# p6_led_matrix.net
KiCad netlist of a schematic drawn in Altium Designer
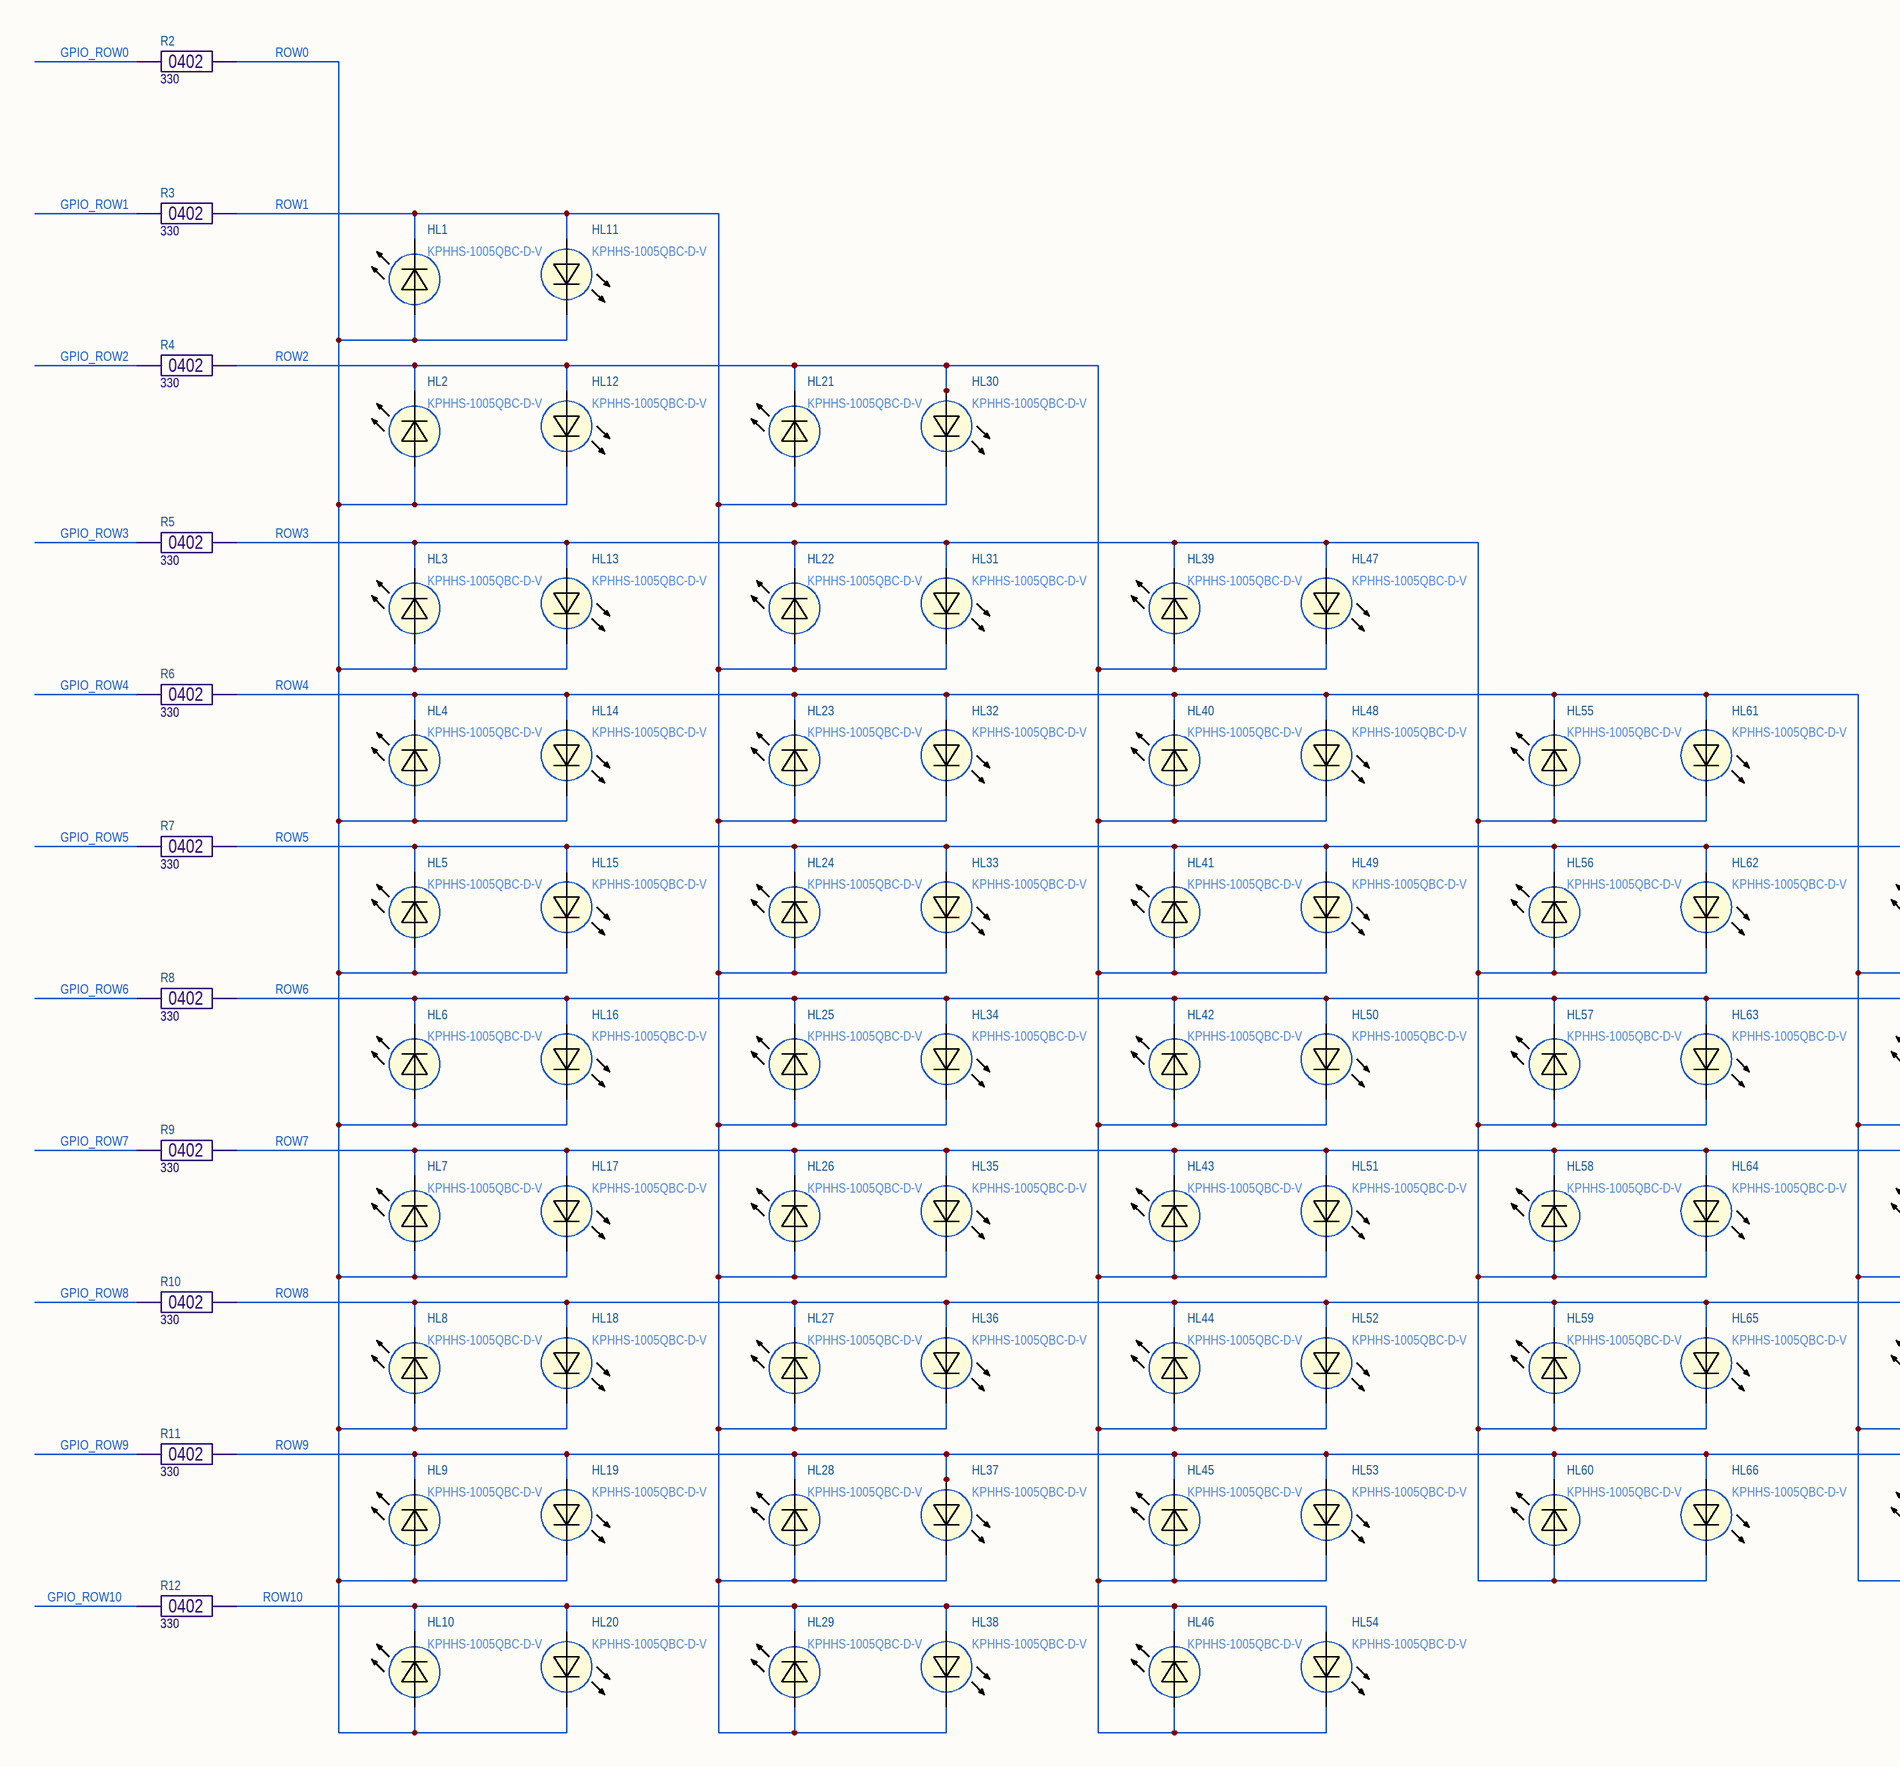
[diagram p0: p6_led_matrix.SchDoc, left]
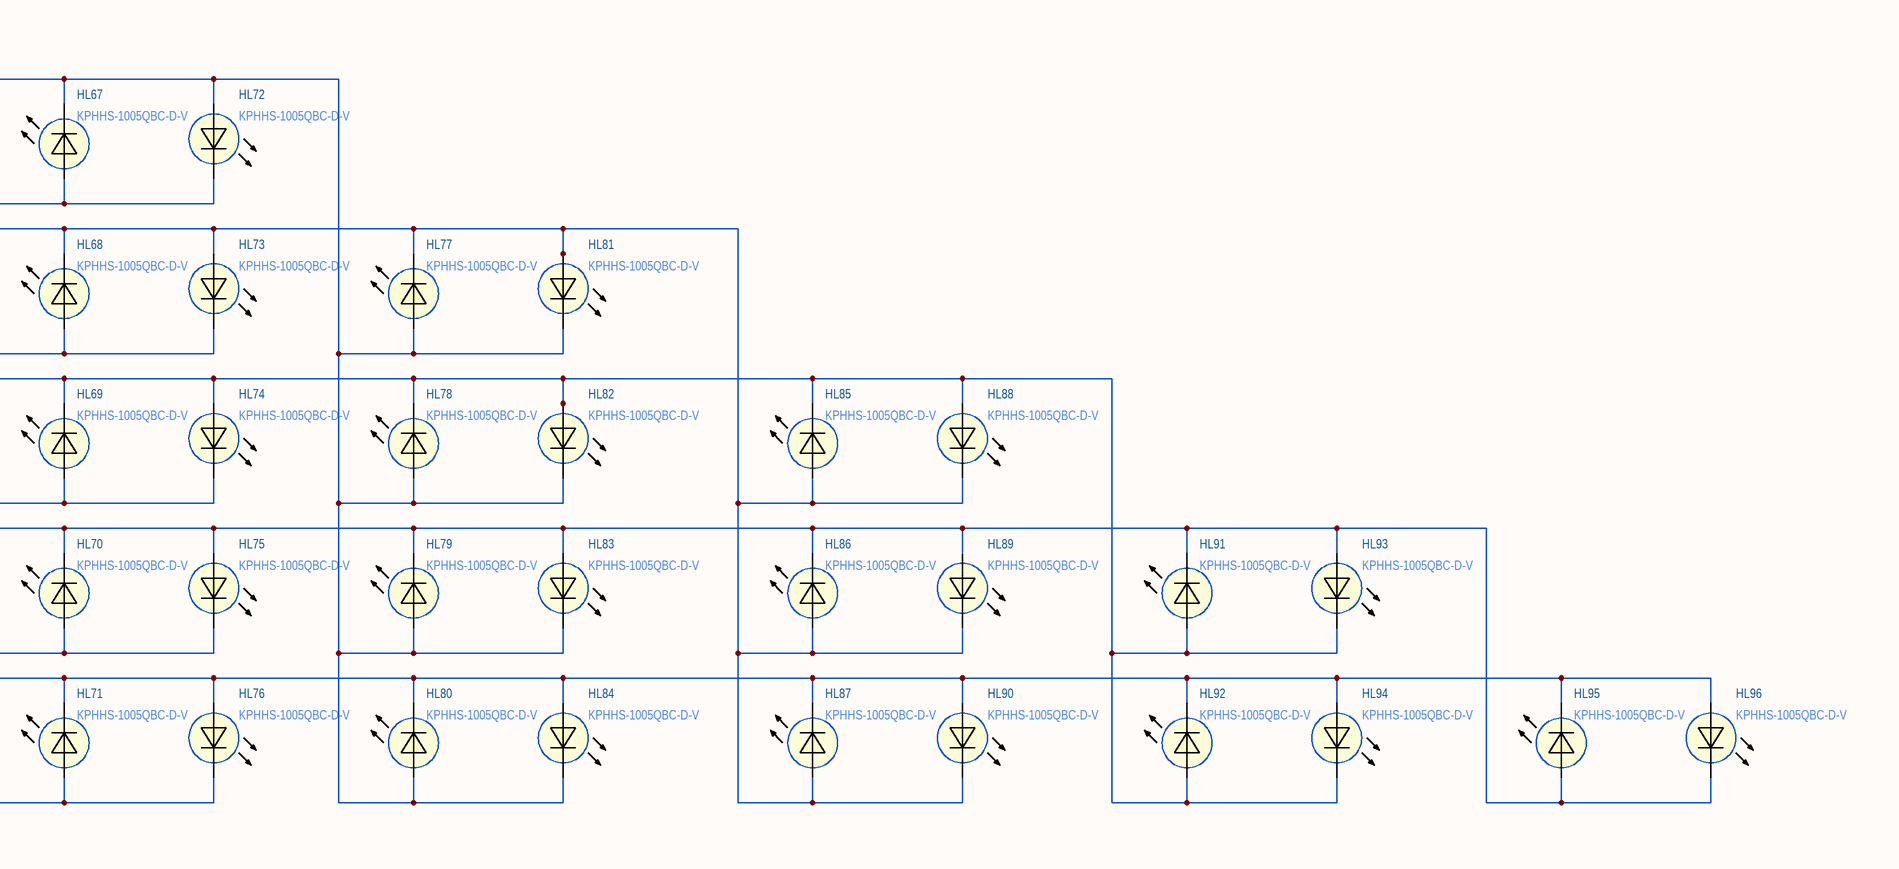
[diagram p1: p6_led_matrix.SchDoc, right]

(export (version "E")
  (design (tool "Eeschema 10.0.6"))
  (components
    (comp (ref "HL1")
      (value "KPHHS-1005QBC-D-V")
      (footprint "PcbLib_Others:LED0402B")
      (description "Blue led (package case 0402)")
      (fields (field (name "MANUFACTURER") "Kingbright Company LLC."))
      (libsource (lib "Schlib_Kingbright") (part "KPHHS-1005QBC-D-V"))
    )
    (comp (ref "HL2")
      (value "KPHHS-1005QBC-D-V")
      (footprint "PcbLib_Others:LED0402B")
      (description "Blue led (package case 0402)")
      (fields (field (name "MANUFACTURER") "Kingbright Company LLC."))
      (libsource (lib "Schlib_Kingbright") (part "KPHHS-1005QBC-D-V"))
    )
    (comp (ref "HL3")
      (value "KPHHS-1005QBC-D-V")
      (footprint "PcbLib_Others:LED0402B")
      (description "Blue led (package case 0402)")
      (fields (field (name "MANUFACTURER") "Kingbright Company LLC."))
      (libsource (lib "Schlib_Kingbright") (part "KPHHS-1005QBC-D-V"))
    )
    (comp (ref "HL4")
      (value "KPHHS-1005QBC-D-V")
      (footprint "PcbLib_Others:LED0402B")
      (description "Blue led (package case 0402)")
      (fields (field (name "MANUFACTURER") "Kingbright Company LLC."))
      (libsource (lib "Schlib_Kingbright") (part "KPHHS-1005QBC-D-V"))
    )
    (comp (ref "HL5")
      (value "KPHHS-1005QBC-D-V")
      (footprint "PcbLib_Others:LED0402B")
      (description "Blue led (package case 0402)")
      (fields (field (name "MANUFACTURER") "Kingbright Company LLC."))
      (libsource (lib "Schlib_Kingbright") (part "KPHHS-1005QBC-D-V"))
    )
    (comp (ref "HL6")
      (value "KPHHS-1005QBC-D-V")
      (footprint "PcbLib_Others:LED0402B")
      (description "Blue led (package case 0402)")
      (fields (field (name "MANUFACTURER") "Kingbright Company LLC."))
      (libsource (lib "Schlib_Kingbright") (part "KPHHS-1005QBC-D-V"))
    )
    (comp (ref "HL7")
      (value "KPHHS-1005QBC-D-V")
      (footprint "PcbLib_Others:LED0402B")
      (description "Blue led (package case 0402)")
      (fields (field (name "MANUFACTURER") "Kingbright Company LLC."))
      (libsource (lib "Schlib_Kingbright") (part "KPHHS-1005QBC-D-V"))
    )
    (comp (ref "HL8")
      (value "KPHHS-1005QBC-D-V")
      (footprint "PcbLib_Others:LED0402B")
      (description "Blue led (package case 0402)")
      (fields (field (name "MANUFACTURER") "Kingbright Company LLC."))
      (libsource (lib "Schlib_Kingbright") (part "KPHHS-1005QBC-D-V"))
    )
    (comp (ref "HL9")
      (value "KPHHS-1005QBC-D-V")
      (footprint "PcbLib_Others:LED0402B")
      (description "Blue led (package case 0402)")
      (fields (field (name "MANUFACTURER") "Kingbright Company LLC."))
      (libsource (lib "Schlib_Kingbright") (part "KPHHS-1005QBC-D-V"))
    )
    (comp (ref "HL10")
      (value "KPHHS-1005QBC-D-V")
      (footprint "PcbLib_Others:LED0402B")
      (description "Blue led (package case 0402)")
      (fields (field (name "MANUFACTURER") "Kingbright Company LLC."))
      (libsource (lib "Schlib_Kingbright") (part "KPHHS-1005QBC-D-V"))
    )
    (comp (ref "HL11")
      (value "KPHHS-1005QBC-D-V")
      (footprint "PcbLib_Others:LED0402B")
      (description "Blue led (package case 0402)")
      (fields (field (name "MANUFACTURER") "Kingbright Company LLC."))
      (libsource (lib "Schlib_Kingbright") (part "KPHHS-1005QBC-D-V"))
    )
    (comp (ref "HL12")
      (value "KPHHS-1005QBC-D-V")
      (footprint "PcbLib_Others:LED0402B")
      (description "Blue led (package case 0402)")
      (fields (field (name "MANUFACTURER") "Kingbright Company LLC."))
      (libsource (lib "Schlib_Kingbright") (part "KPHHS-1005QBC-D-V"))
    )
    (comp (ref "HL13")
      (value "KPHHS-1005QBC-D-V")
      (footprint "PcbLib_Others:LED0402B")
      (description "Blue led (package case 0402)")
      (fields (field (name "MANUFACTURER") "Kingbright Company LLC."))
      (libsource (lib "Schlib_Kingbright") (part "KPHHS-1005QBC-D-V"))
    )
    (comp (ref "HL14")
      (value "KPHHS-1005QBC-D-V")
      (footprint "PcbLib_Others:LED0402B")
      (description "Blue led (package case 0402)")
      (fields (field (name "MANUFACTURER") "Kingbright Company LLC."))
      (libsource (lib "Schlib_Kingbright") (part "KPHHS-1005QBC-D-V"))
    )
    (comp (ref "HL15")
      (value "KPHHS-1005QBC-D-V")
      (footprint "PcbLib_Others:LED0402B")
      (description "Blue led (package case 0402)")
      (fields (field (name "MANUFACTURER") "Kingbright Company LLC."))
      (libsource (lib "Schlib_Kingbright") (part "KPHHS-1005QBC-D-V"))
    )
    (comp (ref "HL16")
      (value "KPHHS-1005QBC-D-V")
      (footprint "PcbLib_Others:LED0402B")
      (description "Blue led (package case 0402)")
      (fields (field (name "MANUFACTURER") "Kingbright Company LLC."))
      (libsource (lib "Schlib_Kingbright") (part "KPHHS-1005QBC-D-V"))
    )
    (comp (ref "HL17")
      (value "KPHHS-1005QBC-D-V")
      (footprint "PcbLib_Others:LED0402B")
      (description "Blue led (package case 0402)")
      (fields (field (name "MANUFACTURER") "Kingbright Company LLC."))
      (libsource (lib "Schlib_Kingbright") (part "KPHHS-1005QBC-D-V"))
    )
    (comp (ref "HL18")
      (value "KPHHS-1005QBC-D-V")
      (footprint "PcbLib_Others:LED0402B")
      (description "Blue led (package case 0402)")
      (fields (field (name "MANUFACTURER") "Kingbright Company LLC."))
      (libsource (lib "Schlib_Kingbright") (part "KPHHS-1005QBC-D-V"))
    )
    (comp (ref "HL19")
      (value "KPHHS-1005QBC-D-V")
      (footprint "PcbLib_Others:LED0402B")
      (description "Blue led (package case 0402)")
      (fields (field (name "MANUFACTURER") "Kingbright Company LLC."))
      (libsource (lib "Schlib_Kingbright") (part "KPHHS-1005QBC-D-V"))
    )
    (comp (ref "HL20")
      (value "KPHHS-1005QBC-D-V")
      (footprint "PcbLib_Others:LED0402B")
      (description "Blue led (package case 0402)")
      (fields (field (name "MANUFACTURER") "Kingbright Company LLC."))
      (libsource (lib "Schlib_Kingbright") (part "KPHHS-1005QBC-D-V"))
    )
    (comp (ref "HL21")
      (value "KPHHS-1005QBC-D-V")
      (footprint "PcbLib_Others:LED0402B")
      (description "Blue led (package case 0402)")
      (fields (field (name "MANUFACTURER") "Kingbright Company LLC."))
      (libsource (lib "Schlib_Kingbright") (part "KPHHS-1005QBC-D-V"))
    )
    (comp (ref "HL22")
      (value "KPHHS-1005QBC-D-V")
      (footprint "PcbLib_Others:LED0402B")
      (description "Blue led (package case 0402)")
      (fields (field (name "MANUFACTURER") "Kingbright Company LLC."))
      (libsource (lib "Schlib_Kingbright") (part "KPHHS-1005QBC-D-V"))
    )
    (comp (ref "HL23")
      (value "KPHHS-1005QBC-D-V")
      (footprint "PcbLib_Others:LED0402B")
      (description "Blue led (package case 0402)")
      (fields (field (name "MANUFACTURER") "Kingbright Company LLC."))
      (libsource (lib "Schlib_Kingbright") (part "KPHHS-1005QBC-D-V"))
    )
    (comp (ref "HL24")
      (value "KPHHS-1005QBC-D-V")
      (footprint "PcbLib_Others:LED0402B")
      (description "Blue led (package case 0402)")
      (fields (field (name "MANUFACTURER") "Kingbright Company LLC."))
      (libsource (lib "Schlib_Kingbright") (part "KPHHS-1005QBC-D-V"))
    )
    (comp (ref "HL25")
      (value "KPHHS-1005QBC-D-V")
      (footprint "PcbLib_Others:LED0402B")
      (description "Blue led (package case 0402)")
      (fields (field (name "MANUFACTURER") "Kingbright Company LLC."))
      (libsource (lib "Schlib_Kingbright") (part "KPHHS-1005QBC-D-V"))
    )
    (comp (ref "HL26")
      (value "KPHHS-1005QBC-D-V")
      (footprint "PcbLib_Others:LED0402B")
      (description "Blue led (package case 0402)")
      (fields (field (name "MANUFACTURER") "Kingbright Company LLC."))
      (libsource (lib "Schlib_Kingbright") (part "KPHHS-1005QBC-D-V"))
    )
    (comp (ref "HL27")
      (value "KPHHS-1005QBC-D-V")
      (footprint "PcbLib_Others:LED0402B")
      (description "Blue led (package case 0402)")
      (fields (field (name "MANUFACTURER") "Kingbright Company LLC."))
      (libsource (lib "Schlib_Kingbright") (part "KPHHS-1005QBC-D-V"))
    )
    (comp (ref "HL28")
      (value "KPHHS-1005QBC-D-V")
      (footprint "PcbLib_Others:LED0402B")
      (description "Blue led (package case 0402)")
      (fields (field (name "MANUFACTURER") "Kingbright Company LLC."))
      (libsource (lib "Schlib_Kingbright") (part "KPHHS-1005QBC-D-V"))
    )
    (comp (ref "HL29")
      (value "KPHHS-1005QBC-D-V")
      (footprint "PcbLib_Others:LED0402B")
      (description "Blue led (package case 0402)")
      (fields (field (name "MANUFACTURER") "Kingbright Company LLC."))
      (libsource (lib "Schlib_Kingbright") (part "KPHHS-1005QBC-D-V"))
    )
    (comp (ref "HL30")
      (value "KPHHS-1005QBC-D-V")
      (footprint "PcbLib_Others:LED0402B")
      (description "Blue led (package case 0402)")
      (fields (field (name "MANUFACTURER") "Kingbright Company LLC."))
      (libsource (lib "Schlib_Kingbright") (part "KPHHS-1005QBC-D-V"))
    )
    (comp (ref "HL31")
      (value "KPHHS-1005QBC-D-V")
      (footprint "PcbLib_Others:LED0402B")
      (description "Blue led (package case 0402)")
      (fields (field (name "MANUFACTURER") "Kingbright Company LLC."))
      (libsource (lib "Schlib_Kingbright") (part "KPHHS-1005QBC-D-V"))
    )
    (comp (ref "HL32")
      (value "KPHHS-1005QBC-D-V")
      (footprint "PcbLib_Others:LED0402B")
      (description "Blue led (package case 0402)")
      (fields (field (name "MANUFACTURER") "Kingbright Company LLC."))
      (libsource (lib "Schlib_Kingbright") (part "KPHHS-1005QBC-D-V"))
    )
    (comp (ref "HL33")
      (value "KPHHS-1005QBC-D-V")
      (footprint "PcbLib_Others:LED0402B")
      (description "Blue led (package case 0402)")
      (fields (field (name "MANUFACTURER") "Kingbright Company LLC."))
      (libsource (lib "Schlib_Kingbright") (part "KPHHS-1005QBC-D-V"))
    )
    (comp (ref "HL34")
      (value "KPHHS-1005QBC-D-V")
      (footprint "PcbLib_Others:LED0402B")
      (description "Blue led (package case 0402)")
      (fields (field (name "MANUFACTURER") "Kingbright Company LLC."))
      (libsource (lib "Schlib_Kingbright") (part "KPHHS-1005QBC-D-V"))
    )
    (comp (ref "HL35")
      (value "KPHHS-1005QBC-D-V")
      (footprint "PcbLib_Others:LED0402B")
      (description "Blue led (package case 0402)")
      (fields (field (name "MANUFACTURER") "Kingbright Company LLC."))
      (libsource (lib "Schlib_Kingbright") (part "KPHHS-1005QBC-D-V"))
    )
    (comp (ref "HL36")
      (value "KPHHS-1005QBC-D-V")
      (footprint "PcbLib_Others:LED0402B")
      (description "Blue led (package case 0402)")
      (fields (field (name "MANUFACTURER") "Kingbright Company LLC."))
      (libsource (lib "Schlib_Kingbright") (part "KPHHS-1005QBC-D-V"))
    )
    (comp (ref "HL37")
      (value "KPHHS-1005QBC-D-V")
      (footprint "PcbLib_Others:LED0402B")
      (description "Blue led (package case 0402)")
      (fields (field (name "MANUFACTURER") "Kingbright Company LLC."))
      (libsource (lib "Schlib_Kingbright") (part "KPHHS-1005QBC-D-V"))
    )
    (comp (ref "HL38")
      (value "KPHHS-1005QBC-D-V")
      (footprint "PcbLib_Others:LED0402B")
      (description "Blue led (package case 0402)")
      (fields (field (name "MANUFACTURER") "Kingbright Company LLC."))
      (libsource (lib "Schlib_Kingbright") (part "KPHHS-1005QBC-D-V"))
    )
    (comp (ref "HL39")
      (value "KPHHS-1005QBC-D-V")
      (footprint "PcbLib_Others:LED0402B")
      (description "Blue led (package case 0402)")
      (fields (field (name "MANUFACTURER") "Kingbright Company LLC."))
      (libsource (lib "Schlib_Kingbright") (part "KPHHS-1005QBC-D-V"))
    )
    (comp (ref "HL40")
      (value "KPHHS-1005QBC-D-V")
      (footprint "PcbLib_Others:LED0402B")
      (description "Blue led (package case 0402)")
      (fields (field (name "MANUFACTURER") "Kingbright Company LLC."))
      (libsource (lib "Schlib_Kingbright") (part "KPHHS-1005QBC-D-V"))
    )
    (comp (ref "HL41")
      (value "KPHHS-1005QBC-D-V")
      (footprint "PcbLib_Others:LED0402B")
      (description "Blue led (package case 0402)")
      (fields (field (name "MANUFACTURER") "Kingbright Company LLC."))
      (libsource (lib "Schlib_Kingbright") (part "KPHHS-1005QBC-D-V"))
    )
    (comp (ref "HL42")
      (value "KPHHS-1005QBC-D-V")
      (footprint "PcbLib_Others:LED0402B")
      (description "Blue led (package case 0402)")
      (fields (field (name "MANUFACTURER") "Kingbright Company LLC."))
      (libsource (lib "Schlib_Kingbright") (part "KPHHS-1005QBC-D-V"))
    )
    (comp (ref "HL43")
      (value "KPHHS-1005QBC-D-V")
      (footprint "PcbLib_Others:LED0402B")
      (description "Blue led (package case 0402)")
      (fields (field (name "MANUFACTURER") "Kingbright Company LLC."))
      (libsource (lib "Schlib_Kingbright") (part "KPHHS-1005QBC-D-V"))
    )
    (comp (ref "HL44")
      (value "KPHHS-1005QBC-D-V")
      (footprint "PcbLib_Others:LED0402B")
      (description "Blue led (package case 0402)")
      (fields (field (name "MANUFACTURER") "Kingbright Company LLC."))
      (libsource (lib "Schlib_Kingbright") (part "KPHHS-1005QBC-D-V"))
    )
    (comp (ref "HL45")
      (value "KPHHS-1005QBC-D-V")
      (footprint "PcbLib_Others:LED0402B")
      (description "Blue led (package case 0402)")
      (fields (field (name "MANUFACTURER") "Kingbright Company LLC."))
      (libsource (lib "Schlib_Kingbright") (part "KPHHS-1005QBC-D-V"))
    )
    (comp (ref "HL46")
      (value "KPHHS-1005QBC-D-V")
      (footprint "PcbLib_Others:LED0402B")
      (description "Blue led (package case 0402)")
      (fields (field (name "MANUFACTURER") "Kingbright Company LLC."))
      (libsource (lib "Schlib_Kingbright") (part "KPHHS-1005QBC-D-V"))
    )
    (comp (ref "HL47")
      (value "KPHHS-1005QBC-D-V")
      (footprint "PcbLib_Others:LED0402B")
      (description "Blue led (package case 0402)")
      (fields (field (name "MANUFACTURER") "Kingbright Company LLC."))
      (libsource (lib "Schlib_Kingbright") (part "KPHHS-1005QBC-D-V"))
    )
    (comp (ref "HL48")
      (value "KPHHS-1005QBC-D-V")
      (footprint "PcbLib_Others:LED0402B")
      (description "Blue led (package case 0402)")
      (fields (field (name "MANUFACTURER") "Kingbright Company LLC."))
      (libsource (lib "Schlib_Kingbright") (part "KPHHS-1005QBC-D-V"))
    )
    (comp (ref "HL49")
      (value "KPHHS-1005QBC-D-V")
      (footprint "PcbLib_Others:LED0402B")
      (description "Blue led (package case 0402)")
      (fields (field (name "MANUFACTURER") "Kingbright Company LLC."))
      (libsource (lib "Schlib_Kingbright") (part "KPHHS-1005QBC-D-V"))
    )
    (comp (ref "HL50")
      (value "KPHHS-1005QBC-D-V")
      (footprint "PcbLib_Others:LED0402B")
      (description "Blue led (package case 0402)")
      (fields (field (name "MANUFACTURER") "Kingbright Company LLC."))
      (libsource (lib "Schlib_Kingbright") (part "KPHHS-1005QBC-D-V"))
    )
    (comp (ref "HL51")
      (value "KPHHS-1005QBC-D-V")
      (footprint "PcbLib_Others:LED0402B")
      (description "Blue led (package case 0402)")
      (fields (field (name "MANUFACTURER") "Kingbright Company LLC."))
      (libsource (lib "Schlib_Kingbright") (part "KPHHS-1005QBC-D-V"))
    )
    (comp (ref "HL52")
      (value "KPHHS-1005QBC-D-V")
      (footprint "PcbLib_Others:LED0402B")
      (description "Blue led (package case 0402)")
      (fields (field (name "MANUFACTURER") "Kingbright Company LLC."))
      (libsource (lib "Schlib_Kingbright") (part "KPHHS-1005QBC-D-V"))
    )
    (comp (ref "HL53")
      (value "KPHHS-1005QBC-D-V")
      (footprint "PcbLib_Others:LED0402B")
      (description "Blue led (package case 0402)")
      (fields (field (name "MANUFACTURER") "Kingbright Company LLC."))
      (libsource (lib "Schlib_Kingbright") (part "KPHHS-1005QBC-D-V"))
    )
    (comp (ref "HL54")
      (value "KPHHS-1005QBC-D-V")
      (footprint "PcbLib_Others:LED0402B")
      (description "Blue led (package case 0402)")
      (fields (field (name "MANUFACTURER") "Kingbright Company LLC."))
      (libsource (lib "Schlib_Kingbright") (part "KPHHS-1005QBC-D-V"))
    )
    (comp (ref "HL55")
      (value "KPHHS-1005QBC-D-V")
      (footprint "PcbLib_Others:LED0402B")
      (description "Blue led (package case 0402)")
      (fields (field (name "MANUFACTURER") "Kingbright Company LLC."))
      (libsource (lib "Schlib_Kingbright") (part "KPHHS-1005QBC-D-V"))
    )
    (comp (ref "HL56")
      (value "KPHHS-1005QBC-D-V")
      (footprint "PcbLib_Others:LED0402B")
      (description "Blue led (package case 0402)")
      (fields (field (name "MANUFACTURER") "Kingbright Company LLC."))
      (libsource (lib "Schlib_Kingbright") (part "KPHHS-1005QBC-D-V"))
    )
    (comp (ref "HL57")
      (value "KPHHS-1005QBC-D-V")
      (footprint "PcbLib_Others:LED0402B")
      (description "Blue led (package case 0402)")
      (fields (field (name "MANUFACTURER") "Kingbright Company LLC."))
      (libsource (lib "Schlib_Kingbright") (part "KPHHS-1005QBC-D-V"))
    )
    (comp (ref "HL58")
      (value "KPHHS-1005QBC-D-V")
      (footprint "PcbLib_Others:LED0402B")
      (description "Blue led (package case 0402)")
      (fields (field (name "MANUFACTURER") "Kingbright Company LLC."))
      (libsource (lib "Schlib_Kingbright") (part "KPHHS-1005QBC-D-V"))
    )
    (comp (ref "HL59")
      (value "KPHHS-1005QBC-D-V")
      (footprint "PcbLib_Others:LED0402B")
      (description "Blue led (package case 0402)")
      (fields (field (name "MANUFACTURER") "Kingbright Company LLC."))
      (libsource (lib "Schlib_Kingbright") (part "KPHHS-1005QBC-D-V"))
    )
    (comp (ref "HL60")
      (value "KPHHS-1005QBC-D-V")
      (footprint "PcbLib_Others:LED0402B")
      (description "Blue led (package case 0402)")
      (fields (field (name "MANUFACTURER") "Kingbright Company LLC."))
      (libsource (lib "Schlib_Kingbright") (part "KPHHS-1005QBC-D-V"))
    )
    (comp (ref "HL61")
      (value "KPHHS-1005QBC-D-V")
      (footprint "PcbLib_Others:LED0402B")
      (description "Blue led (package case 0402)")
      (fields (field (name "MANUFACTURER") "Kingbright Company LLC."))
      (libsource (lib "Schlib_Kingbright") (part "KPHHS-1005QBC-D-V"))
    )
    (comp (ref "HL62")
      (value "KPHHS-1005QBC-D-V")
      (footprint "PcbLib_Others:LED0402B")
      (description "Blue led (package case 0402)")
      (fields (field (name "MANUFACTURER") "Kingbright Company LLC."))
      (libsource (lib "Schlib_Kingbright") (part "KPHHS-1005QBC-D-V"))
    )
    (comp (ref "HL63")
      (value "KPHHS-1005QBC-D-V")
      (footprint "PcbLib_Others:LED0402B")
      (description "Blue led (package case 0402)")
      (fields (field (name "MANUFACTURER") "Kingbright Company LLC."))
      (libsource (lib "Schlib_Kingbright") (part "KPHHS-1005QBC-D-V"))
    )
    (comp (ref "HL64")
      (value "KPHHS-1005QBC-D-V")
      (footprint "PcbLib_Others:LED0402B")
      (description "Blue led (package case 0402)")
      (fields (field (name "MANUFACTURER") "Kingbright Company LLC."))
      (libsource (lib "Schlib_Kingbright") (part "KPHHS-1005QBC-D-V"))
    )
    (comp (ref "HL65")
      (value "KPHHS-1005QBC-D-V")
      (footprint "PcbLib_Others:LED0402B")
      (description "Blue led (package case 0402)")
      (fields (field (name "MANUFACTURER") "Kingbright Company LLC."))
      (libsource (lib "Schlib_Kingbright") (part "KPHHS-1005QBC-D-V"))
    )
    (comp (ref "HL66")
      (value "KPHHS-1005QBC-D-V")
      (footprint "PcbLib_Others:LED0402B")
      (description "Blue led (package case 0402)")
      (fields (field (name "MANUFACTURER") "Kingbright Company LLC."))
      (libsource (lib "Schlib_Kingbright") (part "KPHHS-1005QBC-D-V"))
    )
    (comp (ref "HL67")
      (value "KPHHS-1005QBC-D-V")
      (footprint "PcbLib_Others:LED0402B")
      (description "Blue led (package case 0402)")
      (fields (field (name "MANUFACTURER") "Kingbright Company LLC."))
      (libsource (lib "Schlib_Kingbright") (part "KPHHS-1005QBC-D-V"))
    )
    (comp (ref "HL68")
      (value "KPHHS-1005QBC-D-V")
      (footprint "PcbLib_Others:LED0402B")
      (description "Blue led (package case 0402)")
      (fields (field (name "MANUFACTURER") "Kingbright Company LLC."))
      (libsource (lib "Schlib_Kingbright") (part "KPHHS-1005QBC-D-V"))
    )
    (comp (ref "HL69")
      (value "KPHHS-1005QBC-D-V")
      (footprint "PcbLib_Others:LED0402B")
      (description "Blue led (package case 0402)")
      (fields (field (name "MANUFACTURER") "Kingbright Company LLC."))
      (libsource (lib "Schlib_Kingbright") (part "KPHHS-1005QBC-D-V"))
    )
    (comp (ref "HL70")
      (value "KPHHS-1005QBC-D-V")
      (footprint "PcbLib_Others:LED0402B")
      (description "Blue led (package case 0402)")
      (fields (field (name "MANUFACTURER") "Kingbright Company LLC."))
      (libsource (lib "Schlib_Kingbright") (part "KPHHS-1005QBC-D-V"))
    )
    (comp (ref "HL71")
      (value "KPHHS-1005QBC-D-V")
      (footprint "PcbLib_Others:LED0402B")
      (description "Blue led (package case 0402)")
      (fields (field (name "MANUFACTURER") "Kingbright Company LLC."))
      (libsource (lib "Schlib_Kingbright") (part "KPHHS-1005QBC-D-V"))
    )
    (comp (ref "HL72")
      (value "KPHHS-1005QBC-D-V")
      (footprint "PcbLib_Others:LED0402B")
      (description "Blue led (package case 0402)")
      (fields (field (name "MANUFACTURER") "Kingbright Company LLC."))
      (libsource (lib "Schlib_Kingbright") (part "KPHHS-1005QBC-D-V"))
    )
    (comp (ref "HL73")
      (value "KPHHS-1005QBC-D-V")
      (footprint "PcbLib_Others:LED0402B")
      (description "Blue led (package case 0402)")
      (fields (field (name "MANUFACTURER") "Kingbright Company LLC."))
      (libsource (lib "Schlib_Kingbright") (part "KPHHS-1005QBC-D-V"))
    )
    (comp (ref "HL74")
      (value "KPHHS-1005QBC-D-V")
      (footprint "PcbLib_Others:LED0402B")
      (description "Blue led (package case 0402)")
      (fields (field (name "MANUFACTURER") "Kingbright Company LLC."))
      (libsource (lib "Schlib_Kingbright") (part "KPHHS-1005QBC-D-V"))
    )
    (comp (ref "HL75")
      (value "KPHHS-1005QBC-D-V")
      (footprint "PcbLib_Others:LED0402B")
      (description "Blue led (package case 0402)")
      (fields (field (name "MANUFACTURER") "Kingbright Company LLC."))
      (libsource (lib "Schlib_Kingbright") (part "KPHHS-1005QBC-D-V"))
    )
    (comp (ref "HL76")
      (value "KPHHS-1005QBC-D-V")
      (footprint "PcbLib_Others:LED0402B")
      (description "Blue led (package case 0402)")
      (fields (field (name "MANUFACTURER") "Kingbright Company LLC."))
      (libsource (lib "Schlib_Kingbright") (part "KPHHS-1005QBC-D-V"))
    )
    (comp (ref "HL77")
      (value "KPHHS-1005QBC-D-V")
      (footprint "PcbLib_Others:LED0402B")
      (description "Blue led (package case 0402)")
      (fields (field (name "MANUFACTURER") "Kingbright Company LLC."))
      (libsource (lib "Schlib_Kingbright") (part "KPHHS-1005QBC-D-V"))
    )
    (comp (ref "HL78")
      (value "KPHHS-1005QBC-D-V")
      (footprint "PcbLib_Others:LED0402B")
      (description "Blue led (package case 0402)")
      (fields (field (name "MANUFACTURER") "Kingbright Company LLC."))
      (libsource (lib "Schlib_Kingbright") (part "KPHHS-1005QBC-D-V"))
    )
    (comp (ref "HL79")
      (value "KPHHS-1005QBC-D-V")
      (footprint "PcbLib_Others:LED0402B")
      (description "Blue led (package case 0402)")
      (fields (field (name "MANUFACTURER") "Kingbright Company LLC."))
      (libsource (lib "Schlib_Kingbright") (part "KPHHS-1005QBC-D-V"))
    )
    (comp (ref "HL80")
      (value "KPHHS-1005QBC-D-V")
      (footprint "PcbLib_Others:LED0402B")
      (description "Blue led (package case 0402)")
      (fields (field (name "MANUFACTURER") "Kingbright Company LLC."))
      (libsource (lib "Schlib_Kingbright") (part "KPHHS-1005QBC-D-V"))
    )
    (comp (ref "HL81")
      (value "KPHHS-1005QBC-D-V")
      (footprint "PcbLib_Others:LED0402B")
      (description "Blue led (package case 0402)")
      (fields (field (name "MANUFACTURER") "Kingbright Company LLC."))
      (libsource (lib "Schlib_Kingbright") (part "KPHHS-1005QBC-D-V"))
    )
    (comp (ref "HL82")
      (value "KPHHS-1005QBC-D-V")
      (footprint "PcbLib_Others:LED0402B")
      (description "Blue led (package case 0402)")
      (fields (field (name "MANUFACTURER") "Kingbright Company LLC."))
      (libsource (lib "Schlib_Kingbright") (part "KPHHS-1005QBC-D-V"))
    )
    (comp (ref "HL83")
      (value "KPHHS-1005QBC-D-V")
      (footprint "PcbLib_Others:LED0402B")
      (description "Blue led (package case 0402)")
      (fields (field (name "MANUFACTURER") "Kingbright Company LLC."))
      (libsource (lib "Schlib_Kingbright") (part "KPHHS-1005QBC-D-V"))
    )
    (comp (ref "HL84")
      (value "KPHHS-1005QBC-D-V")
      (footprint "PcbLib_Others:LED0402B")
      (description "Blue led (package case 0402)")
      (fields (field (name "MANUFACTURER") "Kingbright Company LLC."))
      (libsource (lib "Schlib_Kingbright") (part "KPHHS-1005QBC-D-V"))
    )
    (comp (ref "HL85")
      (value "KPHHS-1005QBC-D-V")
      (footprint "PcbLib_Others:LED0402B")
      (description "Blue led (package case 0402)")
      (fields (field (name "MANUFACTURER") "Kingbright Company LLC."))
      (libsource (lib "Schlib_Kingbright") (part "KPHHS-1005QBC-D-V"))
    )
    (comp (ref "HL86")
      (value "KPHHS-1005QBC-D-V")
      (footprint "PcbLib_Others:LED0402B")
      (description "Blue led (package case 0402)")
      (fields (field (name "MANUFACTURER") "Kingbright Company LLC."))
      (libsource (lib "Schlib_Kingbright") (part "KPHHS-1005QBC-D-V"))
    )
    (comp (ref "HL87")
      (value "KPHHS-1005QBC-D-V")
      (footprint "PcbLib_Others:LED0402B")
      (description "Blue led (package case 0402)")
      (fields (field (name "MANUFACTURER") "Kingbright Company LLC."))
      (libsource (lib "Schlib_Kingbright") (part "KPHHS-1005QBC-D-V"))
    )
    (comp (ref "HL88")
      (value "KPHHS-1005QBC-D-V")
      (footprint "PcbLib_Others:LED0402B")
      (description "Blue led (package case 0402)")
      (fields (field (name "MANUFACTURER") "Kingbright Company LLC."))
      (libsource (lib "Schlib_Kingbright") (part "KPHHS-1005QBC-D-V"))
    )
    (comp (ref "HL89")
      (value "KPHHS-1005QBC-D-V")
      (footprint "PcbLib_Others:LED0402B")
      (description "Blue led (package case 0402)")
      (fields (field (name "MANUFACTURER") "Kingbright Company LLC."))
      (libsource (lib "Schlib_Kingbright") (part "KPHHS-1005QBC-D-V"))
    )
    (comp (ref "HL90")
      (value "KPHHS-1005QBC-D-V")
      (footprint "PcbLib_Others:LED0402B")
      (description "Blue led (package case 0402)")
      (fields (field (name "MANUFACTURER") "Kingbright Company LLC."))
      (libsource (lib "Schlib_Kingbright") (part "KPHHS-1005QBC-D-V"))
    )
    (comp (ref "HL91")
      (value "KPHHS-1005QBC-D-V")
      (footprint "PcbLib_Others:LED0402B")
      (description "Blue led (package case 0402)")
      (fields (field (name "MANUFACTURER") "Kingbright Company LLC."))
      (libsource (lib "Schlib_Kingbright") (part "KPHHS-1005QBC-D-V"))
    )
    (comp (ref "HL92")
      (value "KPHHS-1005QBC-D-V")
      (footprint "PcbLib_Others:LED0402B")
      (description "Blue led (package case 0402)")
      (fields (field (name "MANUFACTURER") "Kingbright Company LLC."))
      (libsource (lib "Schlib_Kingbright") (part "KPHHS-1005QBC-D-V"))
    )
    (comp (ref "HL93")
      (value "KPHHS-1005QBC-D-V")
      (footprint "PcbLib_Others:LED0402B")
      (description "Blue led (package case 0402)")
      (fields (field (name "MANUFACTURER") "Kingbright Company LLC."))
      (libsource (lib "Schlib_Kingbright") (part "KPHHS-1005QBC-D-V"))
    )
    (comp (ref "HL94")
      (value "KPHHS-1005QBC-D-V")
      (footprint "PcbLib_Others:LED0402B")
      (description "Blue led (package case 0402)")
      (fields (field (name "MANUFACTURER") "Kingbright Company LLC."))
      (libsource (lib "Schlib_Kingbright") (part "KPHHS-1005QBC-D-V"))
    )
    (comp (ref "HL95")
      (value "KPHHS-1005QBC-D-V")
      (footprint "PcbLib_Others:LED0402B")
      (description "Blue led (package case 0402)")
      (fields (field (name "MANUFACTURER") "Kingbright Company LLC."))
      (libsource (lib "Schlib_Kingbright") (part "KPHHS-1005QBC-D-V"))
    )
    (comp (ref "HL96")
      (value "KPHHS-1005QBC-D-V")
      (footprint "PcbLib_Others:LED0402B")
      (description "Blue led (package case 0402)")
      (fields (field (name "MANUFACTURER") "Kingbright Company LLC."))
      (libsource (lib "Schlib_Kingbright") (part "KPHHS-1005QBC-D-V"))
    )
    (comp (ref "R2")
      (value "330")
      (footprint "PcbLib_RC:RES0402B")
      (description "Resistor 0402 package case")
      (fields
        (field (name "TOLERANCE") "± 1 %")
        (field (name "PART NUMBER") "RC0402FR-07330RL")
        (field (name "PACKAGE") "0402")
      )
      (libsource (lib "Schlib_RC") (part "R0402"))
    )
    (comp (ref "R3")
      (value "330")
      (footprint "PcbLib_RC:RES0402B")
      (description "Resistor 0402 package case")
      (fields
        (field (name "TOLERANCE") "± 1 %")
        (field (name "PART NUMBER") "RC0402FR-07330RL")
        (field (name "PACKAGE") "0402")
      )
      (libsource (lib "Schlib_RC") (part "R0402"))
    )
    (comp (ref "R4")
      (value "330")
      (footprint "PcbLib_RC:RES0402B")
      (description "Resistor 0402 package case")
      (fields
        (field (name "TOLERANCE") "± 1 %")
        (field (name "PART NUMBER") "RC0402FR-07330RL")
        (field (name "PACKAGE") "0402")
      )
      (libsource (lib "Schlib_RC") (part "R0402"))
    )
    (comp (ref "R5")
      (value "330")
      (footprint "PcbLib_RC:RES0402B")
      (description "Resistor 0402 package case")
      (fields
        (field (name "TOLERANCE") "± 1 %")
        (field (name "PART NUMBER") "RC0402FR-07330RL")
        (field (name "PACKAGE") "0402")
      )
      (libsource (lib "Schlib_RC") (part "R0402"))
    )
    (comp (ref "R6")
      (value "330")
      (footprint "PcbLib_RC:RES0402B")
      (description "Resistor 0402 package case")
      (fields
        (field (name "TOLERANCE") "± 1 %")
        (field (name "PART NUMBER") "RC0402FR-07330RL")
        (field (name "PACKAGE") "0402")
      )
      (libsource (lib "Schlib_RC") (part "R0402"))
    )
    (comp (ref "R7")
      (value "330")
      (footprint "PcbLib_RC:RES0402B")
      (description "Resistor 0402 package case")
      (fields
        (field (name "TOLERANCE") "± 1 %")
        (field (name "PART NUMBER") "RC0402FR-07330RL")
        (field (name "PACKAGE") "0402")
      )
      (libsource (lib "Schlib_RC") (part "R0402"))
    )
    (comp (ref "R8")
      (value "330")
      (footprint "PcbLib_RC:RES0402B")
      (description "Resistor 0402 package case")
      (fields
        (field (name "TOLERANCE") "± 1 %")
        (field (name "PART NUMBER") "RC0402FR-07330RL")
        (field (name "PACKAGE") "0402")
      )
      (libsource (lib "Schlib_RC") (part "R0402"))
    )
    (comp (ref "R9")
      (value "330")
      (footprint "PcbLib_RC:RES0402B")
      (description "Resistor 0402 package case")
      (fields
        (field (name "TOLERANCE") "± 1 %")
        (field (name "PART NUMBER") "RC0402FR-07330RL")
        (field (name "PACKAGE") "0402")
      )
      (libsource (lib "Schlib_RC") (part "R0402"))
    )
    (comp (ref "R10")
      (value "330")
      (footprint "PcbLib_RC:RES0402B")
      (description "Resistor 0402 package case")
      (fields
        (field (name "TOLERANCE") "± 1 %")
        (field (name "PART NUMBER") "RC0402FR-07330RL")
        (field (name "PACKAGE") "0402")
      )
      (libsource (lib "Schlib_RC") (part "R0402"))
    )
    (comp (ref "R11")
      (value "330")
      (footprint "PcbLib_RC:RES0402B")
      (description "Resistor 0402 package case")
      (fields
        (field (name "TOLERANCE") "± 1 %")
        (field (name "PART NUMBER") "RC0402FR-07330RL")
        (field (name "PACKAGE") "0402")
      )
      (libsource (lib "Schlib_RC") (part "R0402"))
    )
    (comp (ref "R12")
      (value "330")
      (footprint "PcbLib_RC:RES0402B")
      (description "Resistor 0402 package case")
      (fields
        (field (name "TOLERANCE") "± 1 %")
        (field (name "PART NUMBER") "RC0402FR-07330RL")
        (field (name "PACKAGE") "0402")
      )
      (libsource (lib "Schlib_RC") (part "R0402"))
    )
  )
  (nets
    (net (code "1") (name "/GPIO_ROW0") (class "Default")
      (node (ref "R2") (pin "2") (pinfunction "2_2") (pintype "passive"))
    )
    (net (code "2") (name "/GPIO_ROW1") (class "Default")
      (node (ref "R3") (pin "2") (pinfunction "2_2") (pintype "passive"))
    )
    (net (code "3") (name "/GPIO_ROW2") (class "Default")
      (node (ref "R4") (pin "2") (pinfunction "2_2") (pintype "passive"))
    )
    (net (code "4") (name "/GPIO_ROW3") (class "Default")
      (node (ref "R5") (pin "2") (pinfunction "2_2") (pintype "passive"))
    )
    (net (code "5") (name "/GPIO_ROW4") (class "Default")
      (node (ref "R6") (pin "2") (pinfunction "2_2") (pintype "passive"))
    )
    (net (code "6") (name "/GPIO_ROW5") (class "Default")
      (node (ref "R7") (pin "2") (pinfunction "2_2") (pintype "passive"))
    )
    (net (code "7") (name "/GPIO_ROW6") (class "Default")
      (node (ref "R8") (pin "2") (pinfunction "2_2") (pintype "passive"))
    )
    (net (code "8") (name "/GPIO_ROW7") (class "Default")
      (node (ref "R9") (pin "2") (pinfunction "2_2") (pintype "passive"))
    )
    (net (code "9") (name "/GPIO_ROW8") (class "Default")
      (node (ref "R10") (pin "2") (pinfunction "2_2") (pintype "passive"))
    )
    (net (code "10") (name "/GPIO_ROW9") (class "Default")
      (node (ref "R11") (pin "2") (pinfunction "2_2") (pintype "passive"))
    )
    (net (code "11") (name "/GPIO_ROW10") (class "Default")
      (node (ref "R12") (pin "2") (pinfunction "2_2") (pintype "passive"))
    )
    (net (code "12") (name "/ROW0") (class "Default")
      (node (ref "HL1") (pin "2") (pinfunction "2_2") (pintype "passive"))
      (node (ref "HL10") (pin "2") (pinfunction "2_2") (pintype "passive"))
      (node (ref "HL11") (pin "1") (pinfunction "1_1") (pintype "passive"))
      (node (ref "HL12") (pin "1") (pinfunction "1_1") (pintype "passive"))
      (node (ref "HL13") (pin "1") (pinfunction "1_1") (pintype "passive"))
      (node (ref "HL14") (pin "1") (pinfunction "1_1") (pintype "passive"))
      (node (ref "HL15") (pin "1") (pinfunction "1_1") (pintype "passive"))
      (node (ref "HL16") (pin "1") (pinfunction "1_1") (pintype "passive"))
      (node (ref "HL17") (pin "1") (pinfunction "1_1") (pintype "passive"))
      (node (ref "HL18") (pin "1") (pinfunction "1_1") (pintype "passive"))
      (node (ref "HL19") (pin "1") (pinfunction "1_1") (pintype "passive"))
      (node (ref "HL2") (pin "2") (pinfunction "2_2") (pintype "passive"))
      (node (ref "HL20") (pin "1") (pinfunction "1_1") (pintype "passive"))
      (node (ref "HL3") (pin "2") (pinfunction "2_2") (pintype "passive"))
      (node (ref "HL4") (pin "2") (pinfunction "2_2") (pintype "passive"))
      (node (ref "HL5") (pin "2") (pinfunction "2_2") (pintype "passive"))
      (node (ref "HL6") (pin "2") (pinfunction "2_2") (pintype "passive"))
      (node (ref "HL7") (pin "2") (pinfunction "2_2") (pintype "passive"))
      (node (ref "HL8") (pin "2") (pinfunction "2_2") (pintype "passive"))
      (node (ref "HL9") (pin "2") (pinfunction "2_2") (pintype "passive"))
      (node (ref "R2") (pin "1") (pinfunction "1_1") (pintype "passive"))
    )
    (net (code "13") (name "/ROW1") (class "Default")
      (node (ref "HL1") (pin "1") (pinfunction "1_1") (pintype "passive"))
      (node (ref "HL11") (pin "2") (pinfunction "2_2") (pintype "passive"))
      (node (ref "HL21") (pin "2") (pinfunction "2_2") (pintype "passive"))
      (node (ref "HL22") (pin "2") (pinfunction "2_2") (pintype "passive"))
      (node (ref "HL23") (pin "2") (pinfunction "2_2") (pintype "passive"))
      (node (ref "HL24") (pin "2") (pinfunction "2_2") (pintype "passive"))
      (node (ref "HL25") (pin "2") (pinfunction "2_2") (pintype "passive"))
      (node (ref "HL26") (pin "2") (pinfunction "2_2") (pintype "passive"))
      (node (ref "HL27") (pin "2") (pinfunction "2_2") (pintype "passive"))
      (node (ref "HL28") (pin "2") (pinfunction "2_2") (pintype "passive"))
      (node (ref "HL29") (pin "2") (pinfunction "2_2") (pintype "passive"))
      (node (ref "HL30") (pin "1") (pinfunction "1_1") (pintype "passive"))
      (node (ref "HL31") (pin "1") (pinfunction "1_1") (pintype "passive"))
      (node (ref "HL32") (pin "1") (pinfunction "1_1") (pintype "passive"))
      (node (ref "HL33") (pin "1") (pinfunction "1_1") (pintype "passive"))
      (node (ref "HL34") (pin "1") (pinfunction "1_1") (pintype "passive"))
      (node (ref "HL35") (pin "1") (pinfunction "1_1") (pintype "passive"))
      (node (ref "HL36") (pin "1") (pinfunction "1_1") (pintype "passive"))
      (node (ref "HL37") (pin "1") (pinfunction "1_1") (pintype "passive"))
      (node (ref "HL38") (pin "1") (pinfunction "1_1") (pintype "passive"))
      (node (ref "R3") (pin "1") (pinfunction "1_1") (pintype "passive"))
    )
    (net (code "14") (name "/ROW2") (class "Default")
      (node (ref "HL12") (pin "2") (pinfunction "2_2") (pintype "passive"))
      (node (ref "HL2") (pin "1") (pinfunction "1_1") (pintype "passive"))
      (node (ref "HL21") (pin "1") (pinfunction "1_1") (pintype "passive"))
      (node (ref "HL30") (pin "2") (pinfunction "2_2") (pintype "passive"))
      (node (ref "HL39") (pin "2") (pinfunction "2_2") (pintype "passive"))
      (node (ref "HL40") (pin "2") (pinfunction "2_2") (pintype "passive"))
      (node (ref "HL41") (pin "2") (pinfunction "2_2") (pintype "passive"))
      (node (ref "HL42") (pin "2") (pinfunction "2_2") (pintype "passive"))
      (node (ref "HL43") (pin "2") (pinfunction "2_2") (pintype "passive"))
      (node (ref "HL44") (pin "2") (pinfunction "2_2") (pintype "passive"))
      (node (ref "HL45") (pin "2") (pinfunction "2_2") (pintype "passive"))
      (node (ref "HL46") (pin "2") (pinfunction "2_2") (pintype "passive"))
      (node (ref "HL47") (pin "1") (pinfunction "1_1") (pintype "passive"))
      (node (ref "HL48") (pin "1") (pinfunction "1_1") (pintype "passive"))
      (node (ref "HL49") (pin "1") (pinfunction "1_1") (pintype "passive"))
      (node (ref "HL50") (pin "1") (pinfunction "1_1") (pintype "passive"))
      (node (ref "HL51") (pin "1") (pinfunction "1_1") (pintype "passive"))
      (node (ref "HL52") (pin "1") (pinfunction "1_1") (pintype "passive"))
      (node (ref "HL53") (pin "1") (pinfunction "1_1") (pintype "passive"))
      (node (ref "HL54") (pin "1") (pinfunction "1_1") (pintype "passive"))
      (node (ref "R4") (pin "1") (pinfunction "1_1") (pintype "passive"))
    )
    (net (code "15") (name "/ROW3") (class "Default")
      (node (ref "HL13") (pin "2") (pinfunction "2_2") (pintype "passive"))
      (node (ref "HL22") (pin "1") (pinfunction "1_1") (pintype "passive"))
      (node (ref "HL3") (pin "1") (pinfunction "1_1") (pintype "passive"))
      (node (ref "HL31") (pin "2") (pinfunction "2_2") (pintype "passive"))
      (node (ref "HL39") (pin "1") (pinfunction "1_1") (pintype "passive"))
      (node (ref "HL47") (pin "2") (pinfunction "2_2") (pintype "passive"))
      (node (ref "HL55") (pin "2") (pinfunction "2_2") (pintype "passive"))
      (node (ref "HL56") (pin "2") (pinfunction "2_2") (pintype "passive"))
      (node (ref "HL57") (pin "2") (pinfunction "2_2") (pintype "passive"))
      (node (ref "HL58") (pin "2") (pinfunction "2_2") (pintype "passive"))
      (node (ref "HL59") (pin "2") (pinfunction "2_2") (pintype "passive"))
      (node (ref "HL60") (pin "2") (pinfunction "2_2") (pintype "passive"))
      (node (ref "HL61") (pin "1") (pinfunction "1_1") (pintype "passive"))
      (node (ref "HL62") (pin "1") (pinfunction "1_1") (pintype "passive"))
      (node (ref "HL63") (pin "1") (pinfunction "1_1") (pintype "passive"))
      (node (ref "HL64") (pin "1") (pinfunction "1_1") (pintype "passive"))
      (node (ref "HL65") (pin "1") (pinfunction "1_1") (pintype "passive"))
      (node (ref "HL66") (pin "1") (pinfunction "1_1") (pintype "passive"))
      (node (ref "R5") (pin "1") (pinfunction "1_1") (pintype "passive"))
    )
    (net (code "16") (name "/ROW4") (class "Default")
      (node (ref "HL14") (pin "2") (pinfunction "2_2") (pintype "passive"))
      (node (ref "HL23") (pin "1") (pinfunction "1_1") (pintype "passive"))
      (node (ref "HL32") (pin "2") (pinfunction "2_2") (pintype "passive"))
      (node (ref "HL4") (pin "1") (pinfunction "1_1") (pintype "passive"))
      (node (ref "HL40") (pin "1") (pinfunction "1_1") (pintype "passive"))
      (node (ref "HL48") (pin "2") (pinfunction "2_2") (pintype "passive"))
      (node (ref "HL55") (pin "1") (pinfunction "1_1") (pintype "passive"))
      (node (ref "HL61") (pin "2") (pinfunction "2_2") (pintype "passive"))
      (node (ref "HL67") (pin "2") (pinfunction "2_2") (pintype "passive"))
      (node (ref "HL68") (pin "2") (pinfunction "2_2") (pintype "passive"))
      (node (ref "HL69") (pin "2") (pinfunction "2_2") (pintype "passive"))
      (node (ref "HL70") (pin "2") (pinfunction "2_2") (pintype "passive"))
      (node (ref "HL71") (pin "2") (pinfunction "2_2") (pintype "passive"))
      (node (ref "HL72") (pin "1") (pinfunction "1_1") (pintype "passive"))
      (node (ref "HL73") (pin "1") (pinfunction "1_1") (pintype "passive"))
      (node (ref "HL74") (pin "1") (pinfunction "1_1") (pintype "passive"))
      (node (ref "HL75") (pin "1") (pinfunction "1_1") (pintype "passive"))
      (node (ref "HL76") (pin "1") (pinfunction "1_1") (pintype "passive"))
      (node (ref "R6") (pin "1") (pinfunction "1_1") (pintype "passive"))
    )
    (net (code "17") (name "/ROW5") (class "Default")
      (node (ref "HL15") (pin "2") (pinfunction "2_2") (pintype "passive"))
      (node (ref "HL24") (pin "1") (pinfunction "1_1") (pintype "passive"))
      (node (ref "HL33") (pin "2") (pinfunction "2_2") (pintype "passive"))
      (node (ref "HL41") (pin "1") (pinfunction "1_1") (pintype "passive"))
      (node (ref "HL49") (pin "2") (pinfunction "2_2") (pintype "passive"))
      (node (ref "HL5") (pin "1") (pinfunction "1_1") (pintype "passive"))
      (node (ref "HL56") (pin "1") (pinfunction "1_1") (pintype "passive"))
      (node (ref "HL62") (pin "2") (pinfunction "2_2") (pintype "passive"))
      (node (ref "HL67") (pin "1") (pinfunction "1_1") (pintype "passive"))
      (node (ref "HL72") (pin "2") (pinfunction "2_2") (pintype "passive"))
      (node (ref "HL77") (pin "2") (pinfunction "2_2") (pintype "passive"))
      (node (ref "HL78") (pin "2") (pinfunction "2_2") (pintype "passive"))
      (node (ref "HL79") (pin "2") (pinfunction "2_2") (pintype "passive"))
      (node (ref "HL80") (pin "2") (pinfunction "2_2") (pintype "passive"))
      (node (ref "HL81") (pin "1") (pinfunction "1_1") (pintype "passive"))
      (node (ref "HL82") (pin "1") (pinfunction "1_1") (pintype "passive"))
      (node (ref "HL83") (pin "1") (pinfunction "1_1") (pintype "passive"))
      (node (ref "HL84") (pin "1") (pinfunction "1_1") (pintype "passive"))
      (node (ref "R7") (pin "1") (pinfunction "1_1") (pintype "passive"))
    )
    (net (code "18") (name "/ROW6") (class "Default")
      (node (ref "HL16") (pin "2") (pinfunction "2_2") (pintype "passive"))
      (node (ref "HL25") (pin "1") (pinfunction "1_1") (pintype "passive"))
      (node (ref "HL34") (pin "2") (pinfunction "2_2") (pintype "passive"))
      (node (ref "HL42") (pin "1") (pinfunction "1_1") (pintype "passive"))
      (node (ref "HL50") (pin "2") (pinfunction "2_2") (pintype "passive"))
      (node (ref "HL57") (pin "1") (pinfunction "1_1") (pintype "passive"))
      (node (ref "HL6") (pin "1") (pinfunction "1_1") (pintype "passive"))
      (node (ref "HL63") (pin "2") (pinfunction "2_2") (pintype "passive"))
      (node (ref "HL68") (pin "1") (pinfunction "1_1") (pintype "passive"))
      (node (ref "HL73") (pin "2") (pinfunction "2_2") (pintype "passive"))
      (node (ref "HL77") (pin "1") (pinfunction "1_1") (pintype "passive"))
      (node (ref "HL81") (pin "2") (pinfunction "2_2") (pintype "passive"))
      (node (ref "HL85") (pin "2") (pinfunction "2_2") (pintype "passive"))
      (node (ref "HL86") (pin "2") (pinfunction "2_2") (pintype "passive"))
      (node (ref "HL87") (pin "2") (pinfunction "2_2") (pintype "passive"))
      (node (ref "HL88") (pin "1") (pinfunction "1_1") (pintype "passive"))
      (node (ref "HL89") (pin "1") (pinfunction "1_1") (pintype "passive"))
      (node (ref "HL90") (pin "1") (pinfunction "1_1") (pintype "passive"))
      (node (ref "R8") (pin "1") (pinfunction "1_1") (pintype "passive"))
    )
    (net (code "19") (name "/ROW7") (class "Default")
      (node (ref "HL17") (pin "2") (pinfunction "2_2") (pintype "passive"))
      (node (ref "HL26") (pin "1") (pinfunction "1_1") (pintype "passive"))
      (node (ref "HL35") (pin "2") (pinfunction "2_2") (pintype "passive"))
      (node (ref "HL43") (pin "1") (pinfunction "1_1") (pintype "passive"))
      (node (ref "HL51") (pin "2") (pinfunction "2_2") (pintype "passive"))
      (node (ref "HL58") (pin "1") (pinfunction "1_1") (pintype "passive"))
      (node (ref "HL64") (pin "2") (pinfunction "2_2") (pintype "passive"))
      (node (ref "HL69") (pin "1") (pinfunction "1_1") (pintype "passive"))
      (node (ref "HL7") (pin "1") (pinfunction "1_1") (pintype "passive"))
      (node (ref "HL74") (pin "2") (pinfunction "2_2") (pintype "passive"))
      (node (ref "HL78") (pin "1") (pinfunction "1_1") (pintype "passive"))
      (node (ref "HL82") (pin "2") (pinfunction "2_2") (pintype "passive"))
      (node (ref "HL85") (pin "1") (pinfunction "1_1") (pintype "passive"))
      (node (ref "HL88") (pin "2") (pinfunction "2_2") (pintype "passive"))
      (node (ref "HL91") (pin "2") (pinfunction "2_2") (pintype "passive"))
      (node (ref "HL92") (pin "2") (pinfunction "2_2") (pintype "passive"))
      (node (ref "HL93") (pin "1") (pinfunction "1_1") (pintype "passive"))
      (node (ref "HL94") (pin "1") (pinfunction "1_1") (pintype "passive"))
      (node (ref "R9") (pin "1") (pinfunction "1_1") (pintype "passive"))
    )
    (net (code "20") (name "/ROW8") (class "Default")
      (node (ref "HL18") (pin "2") (pinfunction "2_2") (pintype "passive"))
      (node (ref "HL27") (pin "1") (pinfunction "1_1") (pintype "passive"))
      (node (ref "HL36") (pin "2") (pinfunction "2_2") (pintype "passive"))
      (node (ref "HL44") (pin "1") (pinfunction "1_1") (pintype "passive"))
      (node (ref "HL52") (pin "2") (pinfunction "2_2") (pintype "passive"))
      (node (ref "HL59") (pin "1") (pinfunction "1_1") (pintype "passive"))
      (node (ref "HL65") (pin "2") (pinfunction "2_2") (pintype "passive"))
      (node (ref "HL70") (pin "1") (pinfunction "1_1") (pintype "passive"))
      (node (ref "HL75") (pin "2") (pinfunction "2_2") (pintype "passive"))
      (node (ref "HL79") (pin "1") (pinfunction "1_1") (pintype "passive"))
      (node (ref "HL8") (pin "1") (pinfunction "1_1") (pintype "passive"))
      (node (ref "HL83") (pin "2") (pinfunction "2_2") (pintype "passive"))
      (node (ref "HL86") (pin "1") (pinfunction "1_1") (pintype "passive"))
      (node (ref "HL89") (pin "2") (pinfunction "2_2") (pintype "passive"))
      (node (ref "HL91") (pin "1") (pinfunction "1_1") (pintype "passive"))
      (node (ref "HL93") (pin "2") (pinfunction "2_2") (pintype "passive"))
      (node (ref "HL95") (pin "2") (pinfunction "2_2") (pintype "passive"))
      (node (ref "HL96") (pin "1") (pinfunction "1_1") (pintype "passive"))
      (node (ref "R10") (pin "1") (pinfunction "1_1") (pintype "passive"))
    )
    (net (code "21") (name "/ROW9") (class "Default")
      (node (ref "HL19") (pin "2") (pinfunction "2_2") (pintype "passive"))
      (node (ref "HL28") (pin "1") (pinfunction "1_1") (pintype "passive"))
      (node (ref "HL37") (pin "2") (pinfunction "2_2") (pintype "passive"))
      (node (ref "HL45") (pin "1") (pinfunction "1_1") (pintype "passive"))
      (node (ref "HL53") (pin "2") (pinfunction "2_2") (pintype "passive"))
      (node (ref "HL60") (pin "1") (pinfunction "1_1") (pintype "passive"))
      (node (ref "HL66") (pin "2") (pinfunction "2_2") (pintype "passive"))
      (node (ref "HL71") (pin "1") (pinfunction "1_1") (pintype "passive"))
      (node (ref "HL76") (pin "2") (pinfunction "2_2") (pintype "passive"))
      (node (ref "HL80") (pin "1") (pinfunction "1_1") (pintype "passive"))
      (node (ref "HL84") (pin "2") (pinfunction "2_2") (pintype "passive"))
      (node (ref "HL87") (pin "1") (pinfunction "1_1") (pintype "passive"))
      (node (ref "HL9") (pin "1") (pinfunction "1_1") (pintype "passive"))
      (node (ref "HL90") (pin "2") (pinfunction "2_2") (pintype "passive"))
      (node (ref "HL92") (pin "1") (pinfunction "1_1") (pintype "passive"))
      (node (ref "HL94") (pin "2") (pinfunction "2_2") (pintype "passive"))
      (node (ref "HL95") (pin "1") (pinfunction "1_1") (pintype "passive"))
      (node (ref "HL96") (pin "2") (pinfunction "2_2") (pintype "passive"))
      (node (ref "R11") (pin "1") (pinfunction "1_1") (pintype "passive"))
    )
    (net (code "22") (name "/ROW10") (class "Default")
      (node (ref "HL10") (pin "1") (pinfunction "1_1") (pintype "passive"))
      (node (ref "HL20") (pin "2") (pinfunction "2_2") (pintype "passive"))
      (node (ref "HL29") (pin "1") (pinfunction "1_1") (pintype "passive"))
      (node (ref "HL38") (pin "2") (pinfunction "2_2") (pintype "passive"))
      (node (ref "HL46") (pin "1") (pinfunction "1_1") (pintype "passive"))
      (node (ref "HL54") (pin "2") (pinfunction "2_2") (pintype "passive"))
      (node (ref "R12") (pin "1") (pinfunction "1_1") (pintype "passive"))
    )
  )
)
